# main_board.net
KiCad netlist of a schematic drawn in Altium Designer
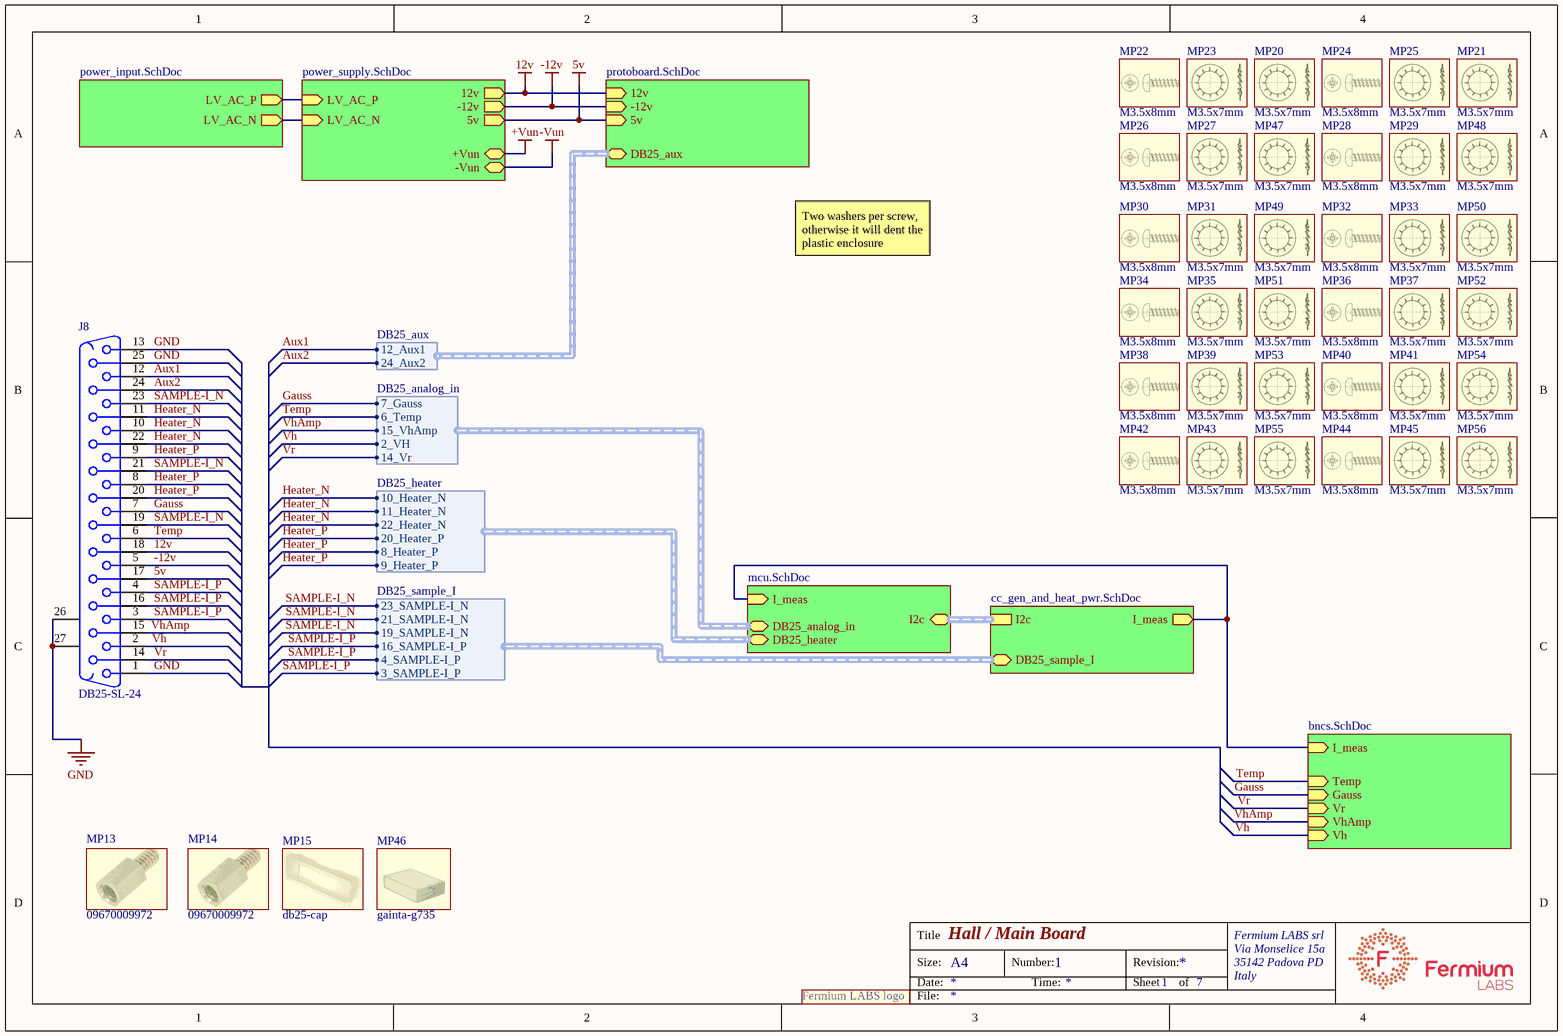
[diagram p0: main_board.SchDoc]

(export (version "E")
  (design (tool "Eeschema 10.0.6"))
  (components
    (comp (ref "J8")
      (value "~")
      (footprint "custom_components:DB25")
      (description "d-sub, 25 pins,  Right Angle")
      (fields
        (field (name "SUPPLIER PART NUMBER 1") "DB25-SL-24")
        (field (name "MANUFACTURER") "ADAM TECH")
        (field (name "MANUFACTURER PART NUMBER") "DB25-SL-24")
      )
      (libsource (lib "Miscellaneous Connectors") (part "D Connector 25"))
    )
    (comp (ref "logo")
      (value "~")
      (footprint "frm-med")
      (libsource (lib "custom_components") (part "fermiumlabs-logo"))
    )
    (comp (ref "MP13")
      (value "09670009972")
      (fields (field (name "MANUFACTURER") "HARTING"))
      (libsource (lib "custom_components") (part "09670009972"))
    )
    (comp (ref "MP14")
      (value "09670009972")
      (fields (field (name "MANUFACTURER") "HARTING"))
      (libsource (lib "custom_components") (part "09670009972"))
    )
    (comp (ref "MP15")
      (value "db25-cap")
      (fields
        (field (name "MANUFACTURER PART NUMBER") "2105-0100-03")
        (field (name "MANUFACTURER") "Encitech")
      )
      (libsource (lib "custom_components") (part "db25-cap"))
    )
    (comp (ref "MP20")
      (value "rondella-dentata-m3.5_1")
      (fields
        (field (name "MANUFACTURER PART NUMBER") "M3.5/BN782 DIN6798J")
        (field (name "MANUFACTURER") "BOSSARD")
        (field (name "SIZE") "M3.5x7mm")
      )
      (libsource (lib "custom_components") (part "rondella-dentata-m3.5_1"))
    )
    (comp (ref "MP21")
      (value "rondella-dentata-m3.5_1")
      (fields
        (field (name "MANUFACTURER PART NUMBER") "M3.5/BN782 DIN6798J")
        (field (name "MANUFACTURER") "BOSSARD")
        (field (name "SIZE") "M3.5x7mm")
      )
      (libsource (lib "custom_components") (part "rondella-dentata-m3.5_1"))
    )
    (comp (ref "MP22")
      (value "screw-3.5x8-plasticc_1")
      (fields
        (field (name "MANUFACTURER PART NUMBER") "M3.5X8/BN82428")
        (field (name "MANUFACTURER") "BOSSARD")
        (field (name "SIZE") "M3.5x8mm")
      )
      (libsource (lib "custom_components") (part "screw-3.5x8-plasticc_1"))
    )
    (comp (ref "MP23")
      (value "rondella-dentata-m3.5_1")
      (fields
        (field (name "MANUFACTURER PART NUMBER") "M3.5/BN782 DIN6798J")
        (field (name "MANUFACTURER") "BOSSARD")
        (field (name "SIZE") "M3.5x7mm")
      )
      (libsource (lib "custom_components") (part "rondella-dentata-m3.5_1"))
    )
    (comp (ref "MP24")
      (value "screw-3.5x8-plasticc_1")
      (fields
        (field (name "MANUFACTURER PART NUMBER") "M3.5X8/BN82428")
        (field (name "MANUFACTURER") "BOSSARD")
        (field (name "SIZE") "M3.5x8mm")
      )
      (libsource (lib "custom_components") (part "screw-3.5x8-plasticc_1"))
    )
    (comp (ref "MP25")
      (value "rondella-dentata-m3.5_1")
      (fields
        (field (name "MANUFACTURER PART NUMBER") "M3.5/BN782 DIN6798J")
        (field (name "MANUFACTURER") "BOSSARD")
        (field (name "SIZE") "M3.5x7mm")
      )
      (libsource (lib "custom_components") (part "rondella-dentata-m3.5_1"))
    )
    (comp (ref "MP26")
      (value "screw-3.5x8-plasticc_1")
      (fields
        (field (name "MANUFACTURER PART NUMBER") "M3.5X8/BN82428")
        (field (name "MANUFACTURER") "BOSSARD")
        (field (name "SIZE") "M3.5x8mm")
      )
      (libsource (lib "custom_components") (part "screw-3.5x8-plasticc_1"))
    )
    (comp (ref "MP27")
      (value "rondella-dentata-m3.5_1")
      (fields
        (field (name "MANUFACTURER PART NUMBER") "M3.5/BN782 DIN6798J")
        (field (name "MANUFACTURER") "BOSSARD")
        (field (name "SIZE") "M3.5x7mm")
      )
      (libsource (lib "custom_components") (part "rondella-dentata-m3.5_1"))
    )
    (comp (ref "MP28")
      (value "screw-3.5x8-plasticc_1")
      (fields
        (field (name "MANUFACTURER PART NUMBER") "M3.5X8/BN82428")
        (field (name "MANUFACTURER") "BOSSARD")
        (field (name "SIZE") "M3.5x8mm")
      )
      (libsource (lib "custom_components") (part "screw-3.5x8-plasticc_1"))
    )
    (comp (ref "MP29")
      (value "rondella-dentata-m3.5_1")
      (fields
        (field (name "MANUFACTURER PART NUMBER") "M3.5/BN782 DIN6798J")
        (field (name "MANUFACTURER") "BOSSARD")
        (field (name "SIZE") "M3.5x7mm")
      )
      (libsource (lib "custom_components") (part "rondella-dentata-m3.5_1"))
    )
    (comp (ref "MP30")
      (value "screw-3.5x8-plasticc_1")
      (fields
        (field (name "MANUFACTURER PART NUMBER") "M3.5X8/BN82428")
        (field (name "MANUFACTURER") "BOSSARD")
        (field (name "SIZE") "M3.5x8mm")
      )
      (libsource (lib "custom_components") (part "screw-3.5x8-plasticc_1"))
    )
    (comp (ref "MP31")
      (value "rondella-dentata-m3.5_1")
      (fields
        (field (name "MANUFACTURER PART NUMBER") "M3.5/BN782 DIN6798J")
        (field (name "MANUFACTURER") "BOSSARD")
        (field (name "SIZE") "M3.5x7mm")
      )
      (libsource (lib "custom_components") (part "rondella-dentata-m3.5_1"))
    )
    (comp (ref "MP32")
      (value "screw-3.5x8-plasticc_1")
      (fields
        (field (name "MANUFACTURER PART NUMBER") "M3.5X8/BN82428")
        (field (name "MANUFACTURER") "BOSSARD")
        (field (name "SIZE") "M3.5x8mm")
      )
      (libsource (lib "custom_components") (part "screw-3.5x8-plasticc_1"))
    )
    (comp (ref "MP33")
      (value "rondella-dentata-m3.5_1")
      (fields
        (field (name "MANUFACTURER PART NUMBER") "M3.5/BN782 DIN6798J")
        (field (name "MANUFACTURER") "BOSSARD")
        (field (name "SIZE") "M3.5x7mm")
      )
      (libsource (lib "custom_components") (part "rondella-dentata-m3.5_1"))
    )
    (comp (ref "MP34")
      (value "screw-3.5x8-plasticc_1")
      (fields
        (field (name "MANUFACTURER PART NUMBER") "M3.5X8/BN82428")
        (field (name "MANUFACTURER") "BOSSARD")
        (field (name "SIZE") "M3.5x8mm")
      )
      (libsource (lib "custom_components") (part "screw-3.5x8-plasticc_1"))
    )
    (comp (ref "MP35")
      (value "rondella-dentata-m3.5_1")
      (fields
        (field (name "MANUFACTURER PART NUMBER") "M3.5/BN782 DIN6798J")
        (field (name "MANUFACTURER") "BOSSARD")
        (field (name "SIZE") "M3.5x7mm")
      )
      (libsource (lib "custom_components") (part "rondella-dentata-m3.5_1"))
    )
    (comp (ref "MP36")
      (value "screw-3.5x8-plasticc_1")
      (fields
        (field (name "MANUFACTURER PART NUMBER") "M3.5X8/BN82428")
        (field (name "MANUFACTURER") "BOSSARD")
        (field (name "SIZE") "M3.5x8mm")
      )
      (libsource (lib "custom_components") (part "screw-3.5x8-plasticc_1"))
    )
    (comp (ref "MP37")
      (value "rondella-dentata-m3.5_1")
      (fields
        (field (name "MANUFACTURER PART NUMBER") "M3.5/BN782 DIN6798J")
        (field (name "MANUFACTURER") "BOSSARD")
        (field (name "SIZE") "M3.5x7mm")
      )
      (libsource (lib "custom_components") (part "rondella-dentata-m3.5_1"))
    )
    (comp (ref "MP38")
      (value "screw-3.5x8-plasticc_1")
      (fields
        (field (name "MANUFACTURER PART NUMBER") "M3.5X8/BN82428")
        (field (name "MANUFACTURER") "BOSSARD")
        (field (name "SIZE") "M3.5x8mm")
      )
      (libsource (lib "custom_components") (part "screw-3.5x8-plasticc_1"))
    )
    (comp (ref "MP39")
      (value "rondella-dentata-m3.5_1")
      (fields
        (field (name "MANUFACTURER PART NUMBER") "M3.5/BN782 DIN6798J")
        (field (name "MANUFACTURER") "BOSSARD")
        (field (name "SIZE") "M3.5x7mm")
      )
      (libsource (lib "custom_components") (part "rondella-dentata-m3.5_1"))
    )
    (comp (ref "MP40")
      (value "screw-3.5x8-plasticc_1")
      (fields
        (field (name "MANUFACTURER PART NUMBER") "M3.5X8/BN82428")
        (field (name "MANUFACTURER") "BOSSARD")
        (field (name "SIZE") "M3.5x8mm")
      )
      (libsource (lib "custom_components") (part "screw-3.5x8-plasticc_1"))
    )
    (comp (ref "MP41")
      (value "rondella-dentata-m3.5_1")
      (fields
        (field (name "MANUFACTURER PART NUMBER") "M3.5/BN782 DIN6798J")
        (field (name "MANUFACTURER") "BOSSARD")
        (field (name "SIZE") "M3.5x7mm")
      )
      (libsource (lib "custom_components") (part "rondella-dentata-m3.5_1"))
    )
    (comp (ref "MP42")
      (value "screw-3.5x8-plasticc_1")
      (fields
        (field (name "MANUFACTURER PART NUMBER") "M3.5X8/BN82428")
        (field (name "MANUFACTURER") "BOSSARD")
        (field (name "SIZE") "M3.5x8mm")
      )
      (libsource (lib "custom_components") (part "screw-3.5x8-plasticc_1"))
    )
    (comp (ref "MP43")
      (value "rondella-dentata-m3.5_1")
      (fields
        (field (name "MANUFACTURER PART NUMBER") "M3.5/BN782 DIN6798J")
        (field (name "MANUFACTURER") "BOSSARD")
        (field (name "SIZE") "M3.5x7mm")
      )
      (libsource (lib "custom_components") (part "rondella-dentata-m3.5_1"))
    )
    (comp (ref "MP44")
      (value "screw-3.5x8-plasticc_1")
      (fields
        (field (name "MANUFACTURER PART NUMBER") "M3.5X8/BN82428")
        (field (name "MANUFACTURER") "BOSSARD")
        (field (name "SIZE") "M3.5x8mm")
      )
      (libsource (lib "custom_components") (part "screw-3.5x8-plasticc_1"))
    )
    (comp (ref "MP45")
      (value "rondella-dentata-m3.5_1")
      (fields
        (field (name "MANUFACTURER PART NUMBER") "M3.5/BN782 DIN6798J")
        (field (name "MANUFACTURER") "BOSSARD")
        (field (name "SIZE") "M3.5x7mm")
      )
      (libsource (lib "custom_components") (part "rondella-dentata-m3.5_1"))
    )
    (comp (ref "MP46")
      (value "gainta-g735")
      (fields (field (name "MANUFACTURER PART NUMBER") "G735") (field (name "MANUFACTURER") "GAINTA"))
      (libsource (lib "custom_components") (part "gainta-g735"))
    )
    (comp (ref "MP47")
      (value "rondella-dentata-m3.5_1")
      (fields
        (field (name "MANUFACTURER PART NUMBER") "M3.5/BN782 DIN6798J")
        (field (name "MANUFACTURER") "BOSSARD")
        (field (name "SIZE") "M3.5x7mm")
      )
      (libsource (lib "custom_components") (part "rondella-dentata-m3.5_1"))
    )
    (comp (ref "MP48")
      (value "rondella-dentata-m3.5_1")
      (fields
        (field (name "MANUFACTURER PART NUMBER") "M3.5/BN782 DIN6798J")
        (field (name "MANUFACTURER") "BOSSARD")
        (field (name "SIZE") "M3.5x7mm")
      )
      (libsource (lib "custom_components") (part "rondella-dentata-m3.5_1"))
    )
    (comp (ref "MP49")
      (value "rondella-dentata-m3.5_1")
      (fields
        (field (name "MANUFACTURER PART NUMBER") "M3.5/BN782 DIN6798J")
        (field (name "MANUFACTURER") "BOSSARD")
        (field (name "SIZE") "M3.5x7mm")
      )
      (libsource (lib "custom_components") (part "rondella-dentata-m3.5_1"))
    )
    (comp (ref "MP50")
      (value "rondella-dentata-m3.5_1")
      (fields
        (field (name "MANUFACTURER PART NUMBER") "M3.5/BN782 DIN6798J")
        (field (name "MANUFACTURER") "BOSSARD")
        (field (name "SIZE") "M3.5x7mm")
      )
      (libsource (lib "custom_components") (part "rondella-dentata-m3.5_1"))
    )
    (comp (ref "MP51")
      (value "rondella-dentata-m3.5_1")
      (fields
        (field (name "MANUFACTURER PART NUMBER") "M3.5/BN782 DIN6798J")
        (field (name "MANUFACTURER") "BOSSARD")
        (field (name "SIZE") "M3.5x7mm")
      )
      (libsource (lib "custom_components") (part "rondella-dentata-m3.5_1"))
    )
    (comp (ref "MP52")
      (value "rondella-dentata-m3.5_1")
      (fields
        (field (name "MANUFACTURER PART NUMBER") "M3.5/BN782 DIN6798J")
        (field (name "MANUFACTURER") "BOSSARD")
        (field (name "SIZE") "M3.5x7mm")
      )
      (libsource (lib "custom_components") (part "rondella-dentata-m3.5_1"))
    )
    (comp (ref "MP53")
      (value "rondella-dentata-m3.5_1")
      (fields
        (field (name "MANUFACTURER PART NUMBER") "M3.5/BN782 DIN6798J")
        (field (name "MANUFACTURER") "BOSSARD")
        (field (name "SIZE") "M3.5x7mm")
      )
      (libsource (lib "custom_components") (part "rondella-dentata-m3.5_1"))
    )
    (comp (ref "MP54")
      (value "rondella-dentata-m3.5_1")
      (fields
        (field (name "MANUFACTURER PART NUMBER") "M3.5/BN782 DIN6798J")
        (field (name "MANUFACTURER") "BOSSARD")
        (field (name "SIZE") "M3.5x7mm")
      )
      (libsource (lib "custom_components") (part "rondella-dentata-m3.5_1"))
    )
    (comp (ref "MP55")
      (value "rondella-dentata-m3.5_1")
      (fields
        (field (name "MANUFACTURER PART NUMBER") "M3.5/BN782 DIN6798J")
        (field (name "MANUFACTURER") "BOSSARD")
        (field (name "SIZE") "M3.5x7mm")
      )
      (libsource (lib "custom_components") (part "rondella-dentata-m3.5_1"))
    )
    (comp (ref "MP56")
      (value "rondella-dentata-m3.5_1")
      (fields
        (field (name "MANUFACTURER PART NUMBER") "M3.5/BN782 DIN6798J")
        (field (name "MANUFACTURER") "BOSSARD")
        (field (name "SIZE") "M3.5x7mm")
      )
      (libsource (lib "custom_components") (part "rondella-dentata-m3.5_1"))
    )
  )
  (nets
    (net (code "6") (name "-12v") (class "Default")
      (node (ref "J8") (pin "5") (pinfunction "5_5") (pintype "passive"))
    )
    (net (code "8") (name "/Aux1") (class "Default")
      (node (ref "J8") (pin "12") (pinfunction "12_12") (pintype "passive"))
    )
    (net (code "9") (name "/Aux2") (class "Default")
      (node (ref "J8") (pin "24") (pinfunction "24_24") (pintype "passive"))
    )
    (net (code "10") (name "/Gauss") (class "Default")
      (node (ref "J8") (pin "7") (pinfunction "7_7") (pintype "passive"))
    )
    (net (code "11") (name "/Heater_N") (class "Default")
      (node (ref "J8") (pin "10") (pinfunction "10_10") (pintype "passive"))
      (node (ref "J8") (pin "11") (pinfunction "11_11") (pintype "passive"))
      (node (ref "J8") (pin "22") (pinfunction "22_22") (pintype "passive"))
    )
    (net (code "12") (name "/Heater_P") (class "Default")
      (node (ref "J8") (pin "20") (pinfunction "20_20") (pintype "passive"))
      (node (ref "J8") (pin "8") (pinfunction "8_8") (pintype "passive"))
      (node (ref "J8") (pin "9") (pinfunction "9_9") (pintype "passive"))
    )
    (net (code "17") (name "/SAMPLE-I_N") (class "Default")
      (node (ref "J8") (pin "19") (pinfunction "19_19") (pintype "passive"))
      (node (ref "J8") (pin "21") (pinfunction "21_21") (pintype "passive"))
      (node (ref "J8") (pin "23") (pinfunction "23_23") (pintype "passive"))
    )
    (net (code "18") (name "/SAMPLE-I_P") (class "Default")
      (node (ref "J8") (pin "16") (pinfunction "16_16") (pintype "passive"))
      (node (ref "J8") (pin "3") (pinfunction "3_3") (pintype "passive"))
      (node (ref "J8") (pin "4") (pinfunction "4_4") (pintype "passive"))
    )
    (net (code "19") (name "/Temp") (class "Default")
      (node (ref "J8") (pin "6") (pinfunction "6_6") (pintype "passive"))
    )
    (net (code "20") (name "/Vh") (class "Default")
      (node (ref "J8") (pin "2") (pinfunction "2_2") (pintype "passive"))
    )
    (net (code "21") (name "/VhAmp") (class "Default")
      (node (ref "J8") (pin "15") (pinfunction "15_15") (pintype "passive"))
    )
    (net (code "22") (name "/Vr") (class "Default")
      (node (ref "J8") (pin "14") (pinfunction "14_14") (pintype "passive"))
    )
    (net (code "27") (name "5v") (class "Default")
      (node (ref "J8") (pin "17") (pinfunction "17_17") (pintype "passive"))
    )
    (net (code "28") (name "12v") (class "Default")
      (node (ref "J8") (pin "18") (pinfunction "18_18") (pintype "passive"))
    )
    (net (code "29") (name "GND") (class "Default")
      (node (ref "J8") (pin "1") (pinfunction "1_1") (pintype "passive"))
      (node (ref "J8") (pin "13") (pinfunction "13_13") (pintype "passive"))
      (node (ref "J8") (pin "25") (pinfunction "25_25") (pintype "passive"))
      (node (ref "J8") (pin "26") (pinfunction "MH1_26") (pintype "passive"))
      (node (ref "J8") (pin "27") (pinfunction "MH2_27") (pintype "passive"))
    )
  )
)
